# SWDPort.net
KiCad netlist of a schematic drawn in Altium Designer
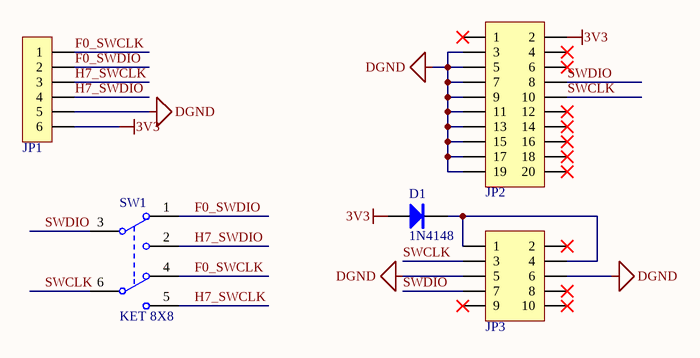
[diagram p0: SWDPort.SchDoc]

(export (version "E")
  (design (tool "Eeschema 10.0.6"))
  (components
    (comp (ref "D1")
      (value "1N4148")
      (footprint "SOD-323")
      (description "开关二极管")
      (libsource (lib "张0.2 - 二极管-整流桥") (part "1N4148"))
    )
    (comp (ref "JP1")
      (value "HDR-1X6")
      (footprint "MX 1.25-WS-6P")
      (description "6P接插件")
      (fields (field (name "版权归属") "源创客"))
      (libsource (lib "4.2   - 接插件-脚距1.25") (part "Header 6"))
    )
    (comp (ref "JP2")
      (value "Header 2X10")
      (footprint "HDR2.54-LI-2x10P")
      (description "10*2P接插件")
      (fields (field (name "版权归属") "源创客"))
      (libsource (lib "4.5   - 接插件-脚距2.54") (part "Header 10X2"))
    )
    (comp (ref "JP3")
      (value "Header 5X2")
      (footprint "HDR2.54-LI-2x5P")
      (description "5*2P接插件")
      (fields (field (name "版权归属") "源创客"))
      (libsource (lib "4.5   - 接插件-脚距2.54") (part "Header 5X2"))
    )
    (comp (ref "SW1")
      (value "KET 8X8")
      (footprint "KFT DIP-8X8")
      (description "8*8自锁开关")
      (fields (field (name "版权归属") "源创客"))
      (libsource (lib "5.1   - 按键-开关") (part "KET 8X8"))
    )
  )
  (nets
    (net (code "1") (name "/F0_SWCLK") (class "Default")
      (node (ref "JP1") (pin "1") (pinfunction "1_1") (pintype "passive"))
      (node (ref "SW1") (pin "4") (pinfunction "NO2_4") (pintype "passive"))
    )
    (net (code "2") (name "/F0_SWDIO") (class "Default")
      (node (ref "JP1") (pin "2") (pinfunction "2_2") (pintype "passive"))
      (node (ref "SW1") (pin "1") (pinfunction "NC1_1") (pintype "passive"))
    )
    (net (code "3") (name "/H7_SWCLK") (class "Default")
      (node (ref "JP1") (pin "3") (pinfunction "3_3") (pintype "passive"))
      (node (ref "SW1") (pin "5") (pinfunction "COM2_5") (pintype "passive"))
    )
    (net (code "4") (name "/H7_SWDIO") (class "Default")
      (node (ref "JP1") (pin "4") (pinfunction "4_4") (pintype "passive"))
      (node (ref "SW1") (pin "2") (pinfunction "COM2_2") (pintype "passive"))
    )
    (net (code "5") (name "/SWCLK") (class "Default")
      (node (ref "JP2") (pin "10") (pinfunction "10_10") (pintype "passive"))
      (node (ref "JP3") (pin "3") (pinfunction "3_3") (pintype "passive"))
      (node (ref "SW1") (pin "6") (pinfunction "NC2_6") (pintype "passive"))
    )
    (net (code "6") (name "/SWDIO") (class "Default")
      (node (ref "JP2") (pin "8") (pinfunction "8_8") (pintype "passive"))
      (node (ref "JP3") (pin "7") (pinfunction "7_7") (pintype "passive"))
      (node (ref "SW1") (pin "3") (pinfunction "NO1_3") (pintype "passive"))
    )
    (net (code "7") (name "3V3") (class "Default")
      (node (ref "D1") (pin "1") (pinfunction "A_1") (pintype "passive"))
      (node (ref "JP1") (pin "6") (pinfunction "6_6") (pintype "passive"))
      (node (ref "JP2") (pin "2") (pinfunction "2_2") (pintype "passive"))
    )
    (net (code "8") (name "DGND") (class "Default")
      (node (ref "JP1") (pin "5") (pinfunction "5_5") (pintype "passive"))
      (node (ref "JP2") (pin "11") (pinfunction "11_11") (pintype "passive"))
      (node (ref "JP2") (pin "13") (pinfunction "13_13") (pintype "passive"))
      (node (ref "JP2") (pin "15") (pinfunction "15_15") (pintype "passive"))
      (node (ref "JP2") (pin "17") (pinfunction "17_17") (pintype "passive"))
      (node (ref "JP2") (pin "19") (pinfunction "19_19") (pintype "passive"))
      (node (ref "JP2") (pin "3") (pinfunction "3_3") (pintype "passive"))
      (node (ref "JP2") (pin "5") (pinfunction "5_5") (pintype "passive"))
      (node (ref "JP2") (pin "7") (pinfunction "7_7") (pintype "passive"))
      (node (ref "JP2") (pin "9") (pinfunction "9_9") (pintype "passive"))
      (node (ref "JP3") (pin "5") (pinfunction "5_5") (pintype "passive"))
      (node (ref "JP3") (pin "6") (pinfunction "6_6") (pintype "passive"))
    )
    (net (code "9") (name "Net-(D1-K)") (class "Default")
      (node (ref "D1") (pin "2") (pinfunction "K_2") (pintype "passive"))
      (node (ref "JP3") (pin "1") (pinfunction "1_1") (pintype "passive"))
      (node (ref "JP3") (pin "4") (pinfunction "4_4") (pintype "passive"))
    )
    (net (code "10") (name "unconnected-(JP2-Pad1)") (class "Default")
      (node (ref "JP2") (pin "1") (pinfunction "1_1") (pintype "passive+no_connect"))
    )
    (net (code "11") (name "unconnected-(JP2-Pad4)") (class "Default")
      (node (ref "JP2") (pin "4") (pinfunction "4_4") (pintype "passive+no_connect"))
    )
    (net (code "12") (name "unconnected-(JP2-Pad6)") (class "Default")
      (node (ref "JP2") (pin "6") (pinfunction "6_6") (pintype "passive+no_connect"))
    )
    (net (code "13") (name "unconnected-(JP2-Pad12)") (class "Default")
      (node (ref "JP2") (pin "12") (pinfunction "12_12") (pintype "passive+no_connect"))
    )
    (net (code "14") (name "unconnected-(JP2-Pad14)") (class "Default")
      (node (ref "JP2") (pin "14") (pinfunction "14_14") (pintype "passive+no_connect"))
    )
    (net (code "15") (name "unconnected-(JP2-Pad16)") (class "Default")
      (node (ref "JP2") (pin "16") (pinfunction "16_16") (pintype "passive+no_connect"))
    )
    (net (code "16") (name "unconnected-(JP2-Pad18)") (class "Default")
      (node (ref "JP2") (pin "18") (pinfunction "18_18") (pintype "passive+no_connect"))
    )
    (net (code "17") (name "unconnected-(JP2-Pad20)") (class "Default")
      (node (ref "JP2") (pin "20") (pinfunction "20_20") (pintype "passive+no_connect"))
    )
    (net (code "18") (name "unconnected-(JP3-Pad2)") (class "Default")
      (node (ref "JP3") (pin "2") (pinfunction "2_2") (pintype "passive+no_connect"))
    )
    (net (code "19") (name "unconnected-(JP3-Pad8)") (class "Default")
      (node (ref "JP3") (pin "8") (pinfunction "8_8") (pintype "passive+no_connect"))
    )
    (net (code "20") (name "unconnected-(JP3-Pad9)") (class "Default")
      (node (ref "JP3") (pin "9") (pinfunction "9_9") (pintype "passive+no_connect"))
    )
    (net (code "21") (name "unconnected-(JP3-Pad10)") (class "Default")
      (node (ref "JP3") (pin "10") (pinfunction "10_10") (pintype "passive+no_connect"))
    )
  )
)
